# 51.net
KiCad netlist of a schematic drawn in Altium Designer
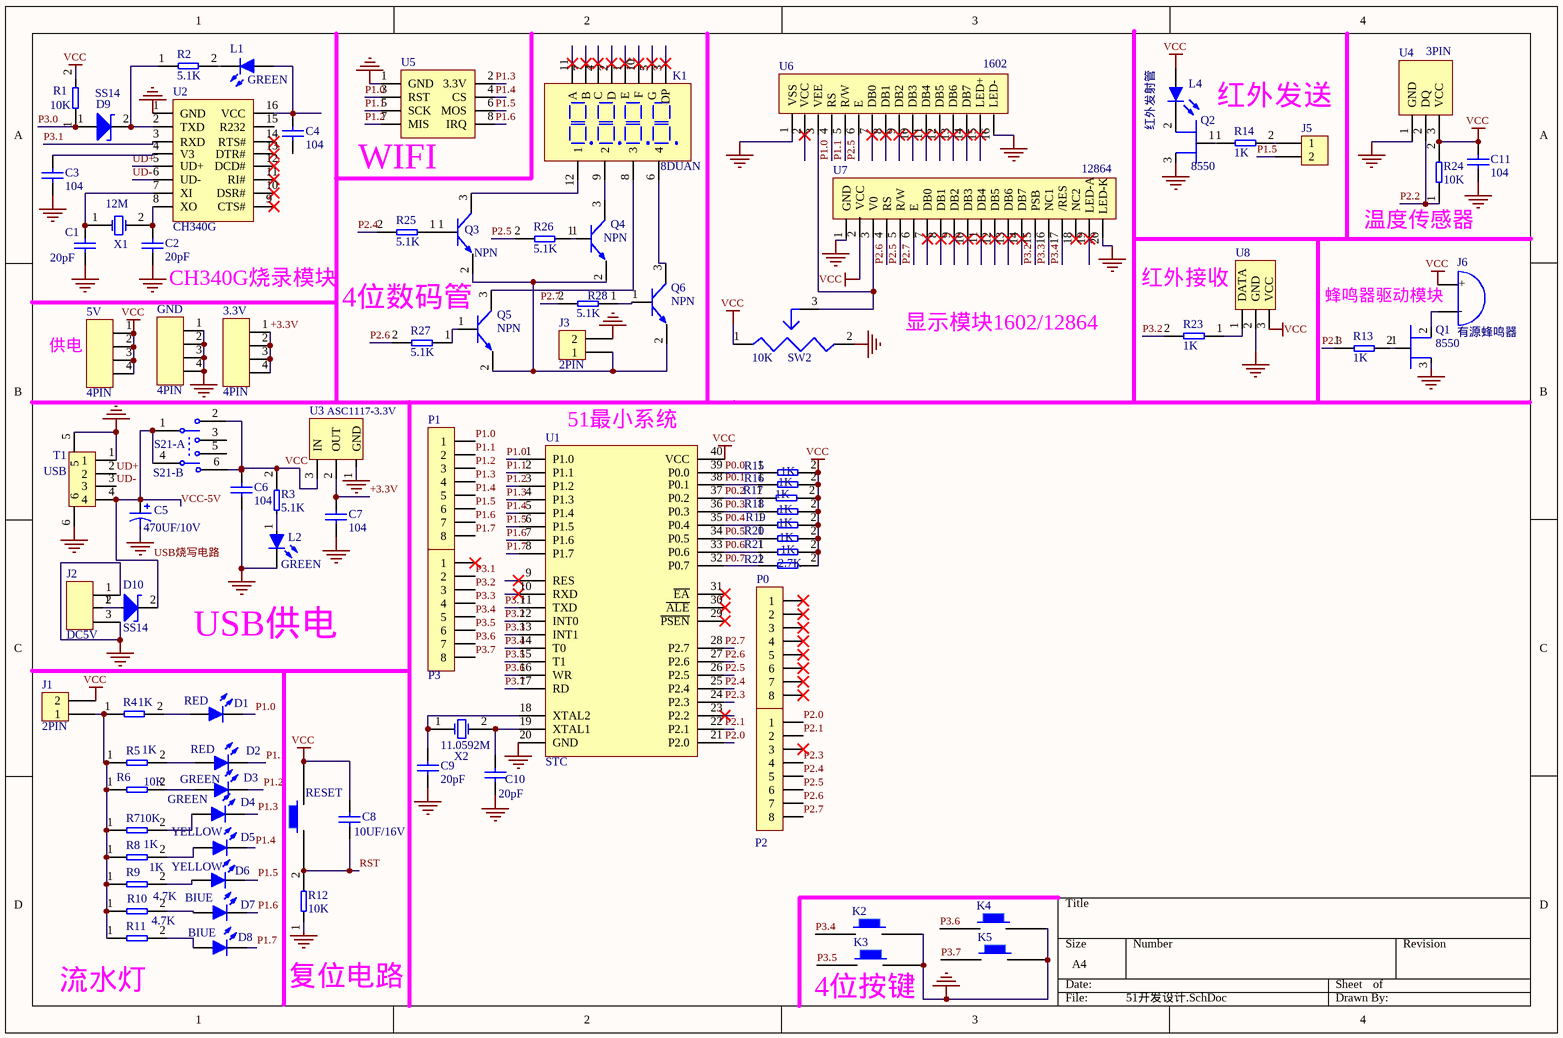
[diagram p0: 51开发设计.SchDoc]

(export (version "E")
  (design (tool "Eeschema 10.0.6"))
  (components
    (comp (ref "3.3V")
      (value "4PIN")
      (footprint "HDR2.54-LI-4P")
      (description "供电")
      (libsource (lib "完整集成") (part "Header-4Pin"))
    )
    (comp (ref "5V")
      (value "4PIN")
      (footprint "HDR2.54-LI-4P")
      (description "供电")
      (libsource (lib "完整集成") (part "Header-4Pin"))
    )
    (comp (ref "C1")
      (value "20pF")
      (footprint "C0603")
      (description "贴片电容")
      (libsource (lib "完整集成") (part "C0603"))
    )
    (comp (ref "C2")
      (value "20pF")
      (footprint "C0603")
      (description "贴片电容")
      (libsource (lib "完整集成") (part "C0603"))
    )
    (comp (ref "C3")
      (value "104")
      (footprint "C0603")
      (description "贴片电容")
      (libsource (lib "完整集成") (part "C0603"))
    )
    (comp (ref "C4")
      (value "104")
      (footprint "C0603")
      (description "贴片电容")
      (libsource (lib "完整集成") (part "C0603"))
    )
    (comp (ref "C5")
      (value "470UF/10V")
      (footprint "CAP-electr-1")
      (description "直插电解电容")
      (libsource (lib "完整集成") (part "CAP-EL-1"))
    )
    (comp (ref "C6")
      (value "104")
      (footprint "C0603")
      (description "贴片电容")
      (libsource (lib "完整集成") (part "C0603"))
    )
    (comp (ref "C7")
      (value "104")
      (footprint "C0603")
      (description "贴片电容")
      (libsource (lib "完整集成") (part "C0603"))
    )
    (comp (ref "C8")
      (value "10UF/16V")
      (footprint "CAP-electr")
      (description "直插电解电容")
      (libsource (lib "完整集成") (part "CAP-EL-2"))
    )
    (comp (ref "C9")
      (value "20pF")
      (footprint "C0603")
      (description "贴片电容")
      (libsource (lib "完整集成") (part "C0603"))
    )
    (comp (ref "C10")
      (value "20pF")
      (footprint "C0603")
      (description "贴片电容")
      (libsource (lib "完整集成") (part "C0603"))
    )
    (comp (ref "C11")
      (value "104")
      (footprint "C0603")
      (description "贴片电容")
      (libsource (lib "完整集成") (part "C0603"))
    )
    (comp (ref "D1")
      (value "RED")
      (footprint "LED-R")
      (description "贴片LED")
      (libsource (lib "完整集成") (part "LED-R"))
    )
    (comp (ref "D2")
      (value "RED")
      (footprint "LED-R")
      (description "贴片LED")
      (libsource (lib "完整集成") (part "LED-R"))
    )
    (comp (ref "D3")
      (value "GREEN")
      (footprint "LED-G")
      (description "贴片LED")
      (libsource (lib "完整集成") (part "LED-G"))
    )
    (comp (ref "D4")
      (value "GREEN")
      (footprint "LED-G")
      (description "贴片LED")
      (libsource (lib "完整集成") (part "LED-G"))
    )
    (comp (ref "D5")
      (value "YELLOW")
      (footprint "LED-Y")
      (description "贴片LED")
      (libsource (lib "完整集成") (part "LED-Y"))
    )
    (comp (ref "D6")
      (value "YELLOW")
      (footprint "LED-Y")
      (description "贴片LED")
      (libsource (lib "完整集成") (part "LED-Y"))
    )
    (comp (ref "D7")
      (value "BIUE")
      (footprint "LED-B")
      (description "贴片LED")
      (libsource (lib "完整集成") (part "LED-B"))
    )
    (comp (ref "D8")
      (value "BIUE")
      (footprint "LED-B")
      (description "贴片LED")
      (libsource (lib "完整集成") (part "LED-B"))
    )
    (comp (ref "D9")
      (value "SS14")
      (footprint "SOD-123")
      (description "二极管")
      (libsource (lib "完整集成") (part "Diode-2"))
    )
    (comp (ref "D10")
      (value "SS14")
      (footprint "SOD-123")
      (description "二极管")
      (libsource (lib "完整集成") (part "Diode-2"))
    )
    (comp (ref "GND")
      (value "4PIN")
      (footprint "HDR2.54-LI-4P")
      (description "供电")
      (libsource (lib "完整集成") (part "Header-4Pin"))
    )
    (comp (ref "J1")
      (value "2PIN")
      (footprint "HDR2.54-LI-2P")
      (description "跳线")
      (libsource (lib "") (part "Header-2Pin_1"))
    )
    (comp (ref "J2")
      (value "DC5V")
      (footprint "Power")
      (description "电源接口")
      (libsource (lib "完整集成") (part "Power"))
    )
    (comp (ref "J3")
      (value "2PIN")
      (footprint "HDR2.54-LI-2P")
      (description "跳线")
      (libsource (lib "") (part "Header-2Pin_1"))
    )
    (comp (ref "J5")
      (value "Header-2Pin")
      (footprint "HDR2.54-LI-2P")
      (description "跳线")
      (libsource (lib "完整集成") (part "Header-2Pin"))
    )
    (comp (ref "J6") (value "有源蜂鸣器") (footprint "Buzzer") (libsource (lib "完整集成") (part "Buzzer")))
    (comp (ref "K1")
      (value "8DUAN")
      (footprint "Digital tube")
      (description "数码管")
      (libsource (lib "完整集成") (part "DISP"))
    )
    (comp (ref "K2")
      (value "Key")
      (footprint "Key")
      (description "轻触按键")
      (libsource (lib "完整集成") (part "Key"))
    )
    (comp (ref "K3")
      (value "Key")
      (footprint "Key")
      (description "轻触按键")
      (libsource (lib "完整集成") (part "Key"))
    )
    (comp (ref "K4")
      (value "Key")
      (footprint "Key")
      (description "轻触按键")
      (libsource (lib "完整集成") (part "Key"))
    )
    (comp (ref "K5")
      (value "Key")
      (footprint "Key")
      (description "轻触按键")
      (libsource (lib "完整集成") (part "Key"))
    )
    (comp (ref "L1")
      (value "GREEN")
      (footprint "LED-G")
      (description "贴片LED")
      (libsource (lib "完整集成") (part "LED-G"))
    )
    (comp (ref "L2")
      (value "GREEN")
      (footprint "LED-G")
      (description "贴片LED")
      (libsource (lib "完整集成") (part "LED-G"))
    )
    (comp (ref "L4") (value "红外发射管") (footprint "LED infrar") (libsource (lib "完整集成") (part "LED infrar")))
    (comp (ref "P0")
      (value "Header-8Pin")
      (footprint "HDR2.54-LI-8P")
      (description "排针8")
      (libsource (lib "完整集成") (part "Header-8Pin"))
    )
    (comp (ref "P1")
      (value "Header-8Pin")
      (footprint "HDR2.54-LI-8P")
      (description "排针8")
      (libsource (lib "完整集成") (part "Header-8Pin"))
    )
    (comp (ref "P2")
      (value "Header-8Pin")
      (footprint "HDR2.54-LI-8P")
      (description "排针8")
      (libsource (lib "完整集成") (part "Header-8Pin"))
    )
    (comp (ref "P3")
      (value "Header-8Pin")
      (footprint "HDR2.54-LI-8P")
      (description "排针8")
      (libsource (lib "完整集成") (part "Header-8Pin"))
    )
    (comp (ref "Q1")
      (value "8550")
      (footprint "SOT-23-3")
      (description "三极管")
      (libsource (lib "完整集成") (part "Triode-3"))
    )
    (comp (ref "Q2")
      (value "8550")
      (footprint "SOT-23-3")
      (description "三极管")
      (libsource (lib "完整集成") (part "Triode-3"))
    )
    (comp (ref "Q3")
      (value "NPN")
      (footprint "SOT-23-3")
      (description "三极管")
      (libsource (lib "完整集成") (part "Triode-2"))
    )
    (comp (ref "Q4")
      (value "NPN")
      (footprint "SOT-23-3")
      (description "三极管")
      (libsource (lib "完整集成") (part "Triode-2"))
    )
    (comp (ref "Q5")
      (value "NPN")
      (footprint "SOT-23-3")
      (description "三极管")
      (libsource (lib "完整集成") (part "Triode-2"))
    )
    (comp (ref "Q6")
      (value "NPN")
      (footprint "SOT-23-3")
      (description "三极管")
      (libsource (lib "完整集成") (part "Triode-2"))
    )
    (comp (ref "R1")
      (value "10K")
      (footprint "R0603")
      (description "贴片电阻")
      (libsource (lib "完整集成") (part "R0603"))
    )
    (comp (ref "R2")
      (value "5.1K")
      (footprint "R0603")
      (description "贴片电阻")
      (libsource (lib "完整集成") (part "R0603"))
    )
    (comp (ref "R3")
      (value "5.1K")
      (footprint "R0603")
      (description "贴片电阻")
      (libsource (lib "完整集成") (part "R0603"))
    )
    (comp (ref "R4")
      (value "1K")
      (footprint "R0603")
      (description "贴片电阻")
      (libsource (lib "完整集成") (part "R0603"))
    )
    (comp (ref "R5")
      (value "1K")
      (footprint "R0603")
      (description "贴片电阻")
      (libsource (lib "完整集成") (part "R0603"))
    )
    (comp (ref "R6")
      (value "10K")
      (footprint "R0603")
      (description "贴片电阻")
      (libsource (lib "完整集成") (part "R0603"))
    )
    (comp (ref "R7")
      (value "10K")
      (footprint "R0603")
      (description "贴片电阻")
      (libsource (lib "完整集成") (part "R0603"))
    )
    (comp (ref "R8")
      (value "1K")
      (footprint "R0603")
      (description "贴片电阻")
      (libsource (lib "完整集成") (part "R0603"))
    )
    (comp (ref "R9")
      (value "1K")
      (footprint "R0603")
      (description "贴片电阻")
      (libsource (lib "完整集成") (part "R0603"))
    )
    (comp (ref "R10")
      (value "4.7K")
      (footprint "R0603")
      (description "贴片电阻")
      (libsource (lib "完整集成") (part "R0603"))
    )
    (comp (ref "R11")
      (value "4.7K")
      (footprint "R0603")
      (description "贴片电阻")
      (libsource (lib "完整集成") (part "R0603"))
    )
    (comp (ref "R12")
      (value "10K")
      (footprint "R0603")
      (description "贴片电阻")
      (libsource (lib "完整集成") (part "R0603"))
    )
    (comp (ref "R13")
      (value "1K")
      (footprint "R0603")
      (description "贴片电阻")
      (libsource (lib "完整集成") (part "R0603"))
    )
    (comp (ref "R14")
      (value "1K")
      (footprint "R0603")
      (description "贴片电阻")
      (libsource (lib "完整集成") (part "R0603"))
    )
    (comp (ref "R15")
      (value "1K")
      (footprint "R0603")
      (description "贴片电阻")
      (libsource (lib "完整集成") (part "R0603"))
    )
    (comp (ref "R16")
      (value "1K")
      (footprint "R0603")
      (description "贴片电阻")
      (libsource (lib "完整集成") (part "R0603"))
    )
    (comp (ref "R17")
      (value "1K")
      (footprint "R0603")
      (description "贴片电阻")
      (libsource (lib "完整集成") (part "R0603"))
    )
    (comp (ref "R18")
      (value "1K")
      (footprint "R0603")
      (description "贴片电阻")
      (libsource (lib "完整集成") (part "R0603"))
    )
    (comp (ref "R19")
      (value "1K")
      (footprint "R0603")
      (description "贴片电阻")
      (libsource (lib "完整集成") (part "R0603"))
    )
    (comp (ref "R20")
      (value "1K")
      (footprint "R0603")
      (description "贴片电阻")
      (libsource (lib "完整集成") (part "R0603"))
    )
    (comp (ref "R21")
      (value "1K")
      (footprint "R0603")
      (description "贴片电阻")
      (libsource (lib "完整集成") (part "R0603"))
    )
    (comp (ref "R22")
      (value "2.7K")
      (footprint "R0603")
      (description "贴片电阻")
      (libsource (lib "完整集成") (part "R0603"))
    )
    (comp (ref "R23")
      (value "1K")
      (footprint "R0603")
      (description "贴片电阻")
      (libsource (lib "完整集成") (part "R0603"))
    )
    (comp (ref "R24")
      (value "10K")
      (footprint "R0603")
      (description "贴片电阻")
      (libsource (lib "完整集成") (part "R0603"))
    )
    (comp (ref "R25")
      (value "5.1K")
      (footprint "R0603")
      (description "贴片电阻")
      (libsource (lib "完整集成") (part "R0603"))
    )
    (comp (ref "R26")
      (value "5.1K")
      (footprint "R0603")
      (description "贴片电阻")
      (libsource (lib "完整集成") (part "R0603"))
    )
    (comp (ref "R27")
      (value "5.1K")
      (footprint "R0603")
      (description "贴片电阻")
      (libsource (lib "完整集成") (part "R0603"))
    )
    (comp (ref "R28")
      (value "5.1K")
      (footprint "R0603")
      (description "贴片电阻")
      (libsource (lib "完整集成") (part "R0603"))
    )
    (comp (ref "RESET")
      (value "Key")
      (footprint "Key")
      (description "轻触按键")
      (libsource (lib "") (part "Key_1"))
    )
    (comp (ref "S21-A")
      (value "S21-B")
      (footprint "SW")
      (description "开关按键")
      (libsource (lib "完整集成") (part "SW"))
    )
    (comp (ref "SW2")
      (value "10K")
      (footprint "Rheostat")
      (description "可调电位器")
      (libsource (lib "完整集成") (part "Rheostat"))
    )
    (comp (ref "T1")
      (value "USB")
      (footprint "USB-MICRO_D")
      (description "USB写入")
      (libsource (lib "完整集成") (part "Micro-usb"))
    )
    (comp (ref "U1")
      (value "STC")
      (footprint "STC89C5X")
      (description "单片机整个")
      (libsource (lib "完整集成") (part "STC89C5X"))
    )
    (comp (ref "U2")
      (value "CH340G")
      (footprint "CH340G")
      (description "电源芯片")
      (libsource (lib "完整集成") (part "CH340G"))
    )
    (comp (ref "U3")
      (value "ASC1117-3.3V")
      (footprint "SOT-223")
      (description "三极管-烧写")
      (libsource (lib "完整集成") (part "Triode-1"))
    )
    (comp (ref "U4")
      (value "3PIN")
      (footprint "HDR2.54-Y-LI-3P")
      (description "温度传感器")
      (libsource (lib "完整集成") (part "Header-3Pin"))
    )
    (comp (ref "U5")
      (value "WIFI")
      (footprint "WiFi Mod")
      (description "WiFi模块")
      (libsource (lib "完整集成") (part "WIFI Module"))
    )
    (comp (ref "U6")
      (value "1602")
      (footprint "HDR2.54-M-LI-16P")
      (description "排母16")
      (libsource (lib "完整集成") (part "Header-16P"))
    )
    (comp (ref "U7")
      (value "12864")
      (footprint "HDR2.54-M-LI-20P")
      (description "排母20")
      (libsource (lib "完整集成") (part "Header-20P"))
    )
    (comp (ref "U8")
      (value "Header-3Pin-1")
      (footprint "HDR2.54-Y-LI-3P")
      (description "红外接收")
      (libsource (lib "完整集成") (part "Header-3Pin-1"))
    )
    (comp (ref "X1")
      (value "12M")
      (footprint "XTAL")
      (description "直插晶振")
      (libsource (lib "完整集成") (part "XTAL"))
    )
    (comp (ref "X2")
      (value "11.0592M")
      (footprint "XTAL")
      (description "直插晶振")
      (libsource (lib "完整集成") (part "XTAL"))
    )
  )
  (nets
    (net (code "1") (name "/+3.3V") (class "Default")
      (node (ref "3.3V") (pin "1") (pinfunction "1_1") (pintype "passive"))
      (node (ref "3.3V") (pin "2") (pinfunction "2_2") (pintype "passive"))
      (node (ref "3.3V") (pin "3") (pinfunction "3_3") (pintype "passive"))
      (node (ref "3.3V") (pin "4") (pinfunction "4_4") (pintype "passive"))
      (node (ref "C7") (pin "2") (pinfunction "2_2") (pintype "passive"))
      (node (ref "U3") (pin "2") (pinfunction "OUT_2") (pintype "passive"))
    )
    (net (code "2") (name "/P0.0") (class "Default")
      (node (ref "R15") (pin "1") (pinfunction "1_1") (pintype "passive"))
      (node (ref "U1") (pin "39") (pinfunction "P0.0_39") (pintype "passive"))
    )
    (net (code "3") (name "/P0.1") (class "Default")
      (node (ref "R16") (pin "1") (pinfunction "1_1") (pintype "passive"))
      (node (ref "U1") (pin "38") (pinfunction "P0.1_38") (pintype "passive"))
    )
    (net (code "4") (name "/P0.2") (class "Default")
      (node (ref "R17") (pin "1") (pinfunction "1_1") (pintype "passive"))
      (node (ref "U1") (pin "37") (pinfunction "P0.2_37") (pintype "passive"))
    )
    (net (code "5") (name "/P0.3") (class "Default")
      (node (ref "R18") (pin "1") (pinfunction "1_1") (pintype "passive"))
      (node (ref "U1") (pin "36") (pinfunction "P0.3_36") (pintype "passive"))
    )
    (net (code "6") (name "/P0.4") (class "Default")
      (node (ref "R19") (pin "1") (pinfunction "1_1") (pintype "passive"))
      (node (ref "U1") (pin "35") (pinfunction "P0.4_35") (pintype "passive"))
    )
    (net (code "7") (name "/P0.5") (class "Default")
      (node (ref "R20") (pin "1") (pinfunction "1_1") (pintype "passive"))
      (node (ref "U1") (pin "34") (pinfunction "P0.5_34") (pintype "passive"))
    )
    (net (code "8") (name "/P0.6") (class "Default")
      (node (ref "R21") (pin "1") (pinfunction "1_1") (pintype "passive"))
      (node (ref "U1") (pin "33") (pinfunction "P0.6_33") (pintype "passive"))
    )
    (net (code "9") (name "/P0.7") (class "Default")
      (node (ref "R22") (pin "1") (pinfunction "1_1") (pintype "passive"))
      (node (ref "U1") (pin "32") (pinfunction "P0.7_32") (pintype "passive"))
    )
    (net (code "10") (name "/P1.0") (class "Default")
      (node (ref "D1") (pin "2") (pinfunction "K_2") (pintype "passive"))
      (node (ref "P1") (pin "1") (pinfunction "1_1") (pintype "passive"))
      (node (ref "U1") (pin "1") (pinfunction "P1.0_1") (pintype "passive"))
      (node (ref "U5") (pin "3") (pinfunction "RST_3") (pintype "passive"))
      (node (ref "U6") (pin "4") (pinfunction "RS_4") (pintype "passive"))
    )
    (net (code "11") (name "/P1.1") (class "Default")
      (node (ref "D2") (pin "2") (pinfunction "K_2") (pintype "passive"))
      (node (ref "P1") (pin "2") (pinfunction "2_2") (pintype "passive"))
      (node (ref "U1") (pin "2") (pinfunction "P1.1_2") (pintype "passive"))
      (node (ref "U5") (pin "5") (pinfunction "SCK_5") (pintype "passive"))
      (node (ref "U6") (pin "5") (pinfunction "R/W_5") (pintype "passive"))
    )
    (net (code "12") (name "/P1.2") (class "Default")
      (node (ref "D3") (pin "2") (pinfunction "K_2") (pintype "passive"))
      (node (ref "P1") (pin "3") (pinfunction "3_3") (pintype "passive"))
      (node (ref "U1") (pin "3") (pinfunction "P1.2_3") (pintype "passive"))
      (node (ref "U5") (pin "7") (pinfunction "MIS_7") (pintype "passive"))
    )
    (net (code "13") (name "/P1.3") (class "Default")
      (node (ref "D4") (pin "2") (pinfunction "K_2") (pintype "passive"))
      (node (ref "P1") (pin "4") (pinfunction "4_4") (pintype "passive"))
      (node (ref "U1") (pin "4") (pinfunction "P1.3_4") (pintype "passive"))
      (node (ref "U5") (pin "2") (pinfunction "3.3V_2") (pintype "passive"))
    )
    (net (code "14") (name "/P1.4") (class "Default")
      (node (ref "D5") (pin "2") (pinfunction "K_2") (pintype "passive"))
      (node (ref "P1") (pin "5") (pinfunction "5_5") (pintype "passive"))
      (node (ref "U1") (pin "5") (pinfunction "P1.4_5") (pintype "passive"))
      (node (ref "U5") (pin "4") (pinfunction "CS_4") (pintype "passive"))
    )
    (net (code "15") (name "/P1.5") (class "Default")
      (node (ref "D6") (pin "2") (pinfunction "K_2") (pintype "passive"))
      (node (ref "J5") (pin "2") (pinfunction "2_2") (pintype "passive"))
      (node (ref "P1") (pin "6") (pinfunction "6_6") (pintype "passive"))
      (node (ref "U1") (pin "6") (pinfunction "P1.5_6") (pintype "passive"))
      (node (ref "U5") (pin "6") (pinfunction "MOS_6") (pintype "passive"))
    )
    (net (code "16") (name "/P1.6") (class "Default")
      (node (ref "D7") (pin "2") (pinfunction "K_2") (pintype "passive"))
      (node (ref "P1") (pin "7") (pinfunction "7_7") (pintype "passive"))
      (node (ref "U1") (pin "7") (pinfunction "P1.6_7") (pintype "passive"))
      (node (ref "U5") (pin "8") (pinfunction "IRQ_8") (pintype "passive"))
    )
    (net (code "17") (name "/P1.7") (class "Default")
      (node (ref "D8") (pin "2") (pinfunction "K_2") (pintype "passive"))
      (node (ref "P1") (pin "8") (pinfunction "8_8") (pintype "passive"))
      (node (ref "U1") (pin "8") (pinfunction "P1.7_8") (pintype "passive"))
    )
    (net (code "18") (name "/P2.0") (class "Default")
      (node (ref "P2") (pin "1") (pinfunction "1_1") (pintype "passive"))
      (node (ref "U1") (pin "21") (pinfunction "P2.0_21") (pintype "passive"))
    )
    (net (code "19") (name "/P2.1") (class "Default")
      (node (ref "P2") (pin "2") (pinfunction "2_2") (pintype "passive"))
      (node (ref "U1") (pin "22") (pinfunction "P2.1_22") (pintype "passive"))
    )
    (net (code "20") (name "/P2.2") (class "Default")
      (node (ref "R24") (pin "1") (pinfunction "1_1") (pintype "passive"))
      (node (ref "U4") (pin "2") (pinfunction "DQ_2") (pintype "passive"))
    )
    (net (code "21") (name "/P2.3") (class "Default")
      (node (ref "P2") (pin "4") (pinfunction "4_4") (pintype "passive"))
      (node (ref "R13") (pin "1") (pinfunction "1_1") (pintype "passive"))
      (node (ref "U1") (pin "24") (pinfunction "P2.3_24") (pintype "passive"))
    )
    (net (code "22") (name "/P2.4") (class "Default")
      (node (ref "P2") (pin "5") (pinfunction "5_5") (pintype "passive"))
      (node (ref "R25") (pin "2") (pinfunction "2_2") (pintype "passive"))
      (node (ref "U1") (pin "25") (pinfunction "P2.4_25") (pintype "passive"))
    )
    (net (code "23") (name "/P2.5") (class "Default")
      (node (ref "P2") (pin "6") (pinfunction "6_6") (pintype "passive"))
      (node (ref "R26") (pin "2") (pinfunction "2_2") (pintype "passive"))
      (node (ref "U1") (pin "26") (pinfunction "P2.5_26") (pintype "passive"))
      (node (ref "U6") (pin "6") (pinfunction "E_6") (pintype "passive"))
      (node (ref "U7") (pin "5") (pinfunction "R/W_5") (pintype "passive"))
    )
    (net (code "24") (name "/P2.6") (class "Default")
      (node (ref "P2") (pin "7") (pinfunction "7_7") (pintype "passive"))
      (node (ref "R27") (pin "2") (pinfunction "2_2") (pintype "passive"))
      (node (ref "U1") (pin "27") (pinfunction "P2.6_27") (pintype "passive"))
      (node (ref "U7") (pin "4") (pinfunction "RS_4") (pintype "passive"))
    )
    (net (code "25") (name "/P2.7") (class "Default")
      (node (ref "P2") (pin "8") (pinfunction "8_8") (pintype "passive"))
      (node (ref "R28") (pin "2") (pinfunction "2_2") (pintype "passive"))
      (node (ref "U1") (pin "28") (pinfunction "P2.7_28") (pintype "passive"))
      (node (ref "U7") (pin "6") (pinfunction "E_6") (pintype "passive"))
    )
    (net (code "26") (name "/P3.0") (class "Default")
      (node (ref "D9") (pin "1") (pinfunction "1_1") (pintype "passive"))
      (node (ref "R1") (pin "1") (pinfunction "1_1") (pintype "passive"))
    )
    (net (code "27") (name "/P3.1") (class "Default")
      (node (ref "P3") (pin "2") (pinfunction "2_2") (pintype "passive"))
      (node (ref "U1") (pin "11") (pinfunction "TXD_11") (pintype "passive"))
      (node (ref "U2") (pin "3") (pinfunction "RXD_3") (pintype "passive"))
    )
    (net (code "28") (name "/P3.2") (class "Default")
      (node (ref "P3") (pin "3") (pinfunction "3_3") (pintype "passive"))
      (node (ref "R23") (pin "2") (pinfunction "2_2") (pintype "passive"))
      (node (ref "U1") (pin "12") (pinfunction "INT0_12") (pintype "passive"))
      (node (ref "U7") (pin "15") (pinfunction "PSB_15") (pintype "passive"))
    )
    (net (code "29") (name "/P3.3") (class "Default")
      (node (ref "P3") (pin "4") (pinfunction "4_4") (pintype "passive"))
      (node (ref "U1") (pin "13") (pinfunction "INT1_13") (pintype "passive"))
      (node (ref "U7") (pin "16") (pinfunction "NC1_16") (pintype "passive"))
    )
    (net (code "30") (name "/P3.4") (class "Default")
      (node (ref "K2") (pin "1") (pinfunction "1_1") (pintype "passive"))
      (node (ref "P3") (pin "5") (pinfunction "5_5") (pintype "passive"))
      (node (ref "U1") (pin "14") (pinfunction "T0_14") (pintype "passive"))
      (node (ref "U7") (pin "17") (pinfunction "/RES_17") (pintype "passive"))
    )
    (net (code "31") (name "/P3.5") (class "Default")
      (node (ref "K3") (pin "1") (pinfunction "1_1") (pintype "passive"))
      (node (ref "P3") (pin "6") (pinfunction "6_6") (pintype "passive"))
      (node (ref "U1") (pin "15") (pinfunction "T1_15") (pintype "passive"))
    )
    (net (code "32") (name "/P3.6") (class "Default")
      (node (ref "K4") (pin "1") (pinfunction "1_1") (pintype "passive"))
      (node (ref "P3") (pin "7") (pinfunction "7_7") (pintype "passive"))
      (node (ref "U1") (pin "16") (pinfunction "WR_16") (pintype "passive"))
    )
    (net (code "33") (name "/P3.7") (class "Default")
      (node (ref "K5") (pin "1") (pinfunction "1_1") (pintype "passive"))
      (node (ref "P3") (pin "8") (pinfunction "8_8") (pintype "passive"))
      (node (ref "U1") (pin "17") (pinfunction "RD_17") (pintype "passive"))
    )
    (net (code "34") (name "/RST") (class "Default")
      (node (ref "C8") (pin "1") (pinfunction "1_1") (pintype "passive"))
      (node (ref "R12") (pin "2") (pinfunction "2_2") (pintype "passive"))
      (node (ref "RESET") (pin "1") (pinfunction "1_1") (pintype "passive"))
    )
    (net (code "35") (name "/UD+") (class "Default")
      (node (ref "T1") (pin "2") (pinfunction "2_2") (pintype "passive"))
      (node (ref "U2") (pin "5") (pinfunction "UD+_5") (pintype "passive"))
    )
    (net (code "36") (name "/UD-") (class "Default")
      (node (ref "T1") (pin "3") (pinfunction "3_3") (pintype "passive"))
      (node (ref "U2") (pin "6") (pinfunction "UD-_6") (pintype "passive"))
    )
    (net (code "37") (name "/USB烧写电路") (class "Default")
      (node (ref "C5") (pin "1") (pinfunction "1_1") (pintype "passive"))
      (node (ref "D10") (pin "2") (pinfunction "2_2") (pintype "passive"))
      (node (ref "S21-A") (pin "1") (pinfunction "1_1") (pintype "passive"))
      (node (ref "S21-A") (pin "4") (pinfunction "4_4") (pintype "passive"))
      (node (ref "T1") (pin "4") (pinfunction "4_4") (pintype "passive"))
    )
    (net (code "38") (name "GND") (class "Default")
      (node (ref "C1") (pin "1") (pinfunction "1_1") (pintype "passive"))
      (node (ref "C10") (pin "1") (pinfunction "1_1") (pintype "passive"))
      (node (ref "C11") (pin "1") (pinfunction "1_1") (pintype "passive"))
      (node (ref "C2") (pin "1") (pinfunction "1_1") (pintype "passive"))
      (node (ref "C3") (pin "1") (pinfunction "1_1") (pintype "passive"))
      (node (ref "C5") (pin "2") (pinfunction "2_2") (pintype "passive"))
      (node (ref "C6") (pin "1") (pinfunction "1_1") (pintype "passive"))
      (node (ref "C7") (pin "1") (pinfunction "1_1") (pintype "passive"))
      (node (ref "C9") (pin "1") (pinfunction "1_1") (pintype "passive"))
      (node (ref "GND") (pin "1") (pinfunction "1_1") (pintype "passive"))
      (node (ref "GND") (pin "2") (pinfunction "2_2") (pintype "passive"))
      (node (ref "GND") (pin "3") (pinfunction "3_3") (pintype "passive"))
      (node (ref "GND") (pin "4") (pinfunction "4_4") (pintype "passive"))
      (node (ref "J2") (pin "1") (pinfunction "1_1") (pintype "passive"))
      (node (ref "J2") (pin "3") (pinfunction "3_3") (pintype "passive"))
      (node (ref "J3") (pin "2") (pinfunction "2_2") (pintype "passive"))
      (node (ref "K2") (pin "2") (pinfunction "2_2") (pintype "passive"))
      (node (ref "K3") (pin "2") (pinfunction "2_2") (pintype "passive"))
      (node (ref "K4") (pin "2") (pinfunction "2_2") (pintype "passive"))
      (node (ref "K5") (pin "2") (pinfunction "2_2") (pintype "passive"))
      (node (ref "L2") (pin "2") (pinfunction "K_2") (pintype "passive"))
      (node (ref "Q1") (pin "3") (pinfunction "3_3") (pintype "passive"))
      (node (ref "Q2") (pin "3") (pinfunction "3_3") (pintype "passive"))
      (node (ref "R12") (pin "1") (pinfunction "1_1") (pintype "passive"))
      (node (ref "SW2") (pin "2") (pinfunction "2_2") (pintype "passive"))
      (node (ref "T1") (pin "1") (pinfunction "1_1") (pintype "passive"))
      (node (ref "T1") (pin "5") (pinfunction "5_5") (pintype "passive"))
      (node (ref "T1") (pin "6") (pinfunction "6_6") (pintype "passive"))
      (node (ref "U1") (pin "20") (pinfunction "GND_20") (pintype "passive"))
      (node (ref "U2") (pin "1") (pinfunction "GND_1") (pintype "passive"))
      (node (ref "U3") (pin "1") (pinfunction "GND_1") (pintype "passive"))
      (node (ref "U4") (pin "1") (pinfunction "GND_1") (pintype "passive"))
      (node (ref "U5") (pin "1") (pinfunction "GND_1") (pintype "passive"))
      (node (ref "U6") (pin "1") (pinfunction "VSS_1") (pintype "passive"))
      (node (ref "U6") (pin "16") (pinfunction "LED-_16") (pintype "passive"))
      (node (ref "U7") (pin "1") (pinfunction "GND_1") (pintype "passive"))
      (node (ref "U7") (pin "20") (pinfunction "LED-K_20") (pintype "passive"))
      (node (ref "U8") (pin "2") (pinfunction "GND_2") (pintype "passive"))
    )
    (net (code "39") (name "Net-(D1-A)") (class "Default")
      (node (ref "D1") (pin "1") (pinfunction "A_1") (pintype "passive"))
      (node (ref "R4") (pin "2") (pinfunction "2_2") (pintype "passive"))
    )
    (net (code "40") (name "Net-(D2-A)") (class "Default")
      (node (ref "D2") (pin "1") (pinfunction "A_1") (pintype "passive"))
      (node (ref "R5") (pin "2") (pinfunction "2_2") (pintype "passive"))
    )
    (net (code "41") (name "Net-(D3-A)") (class "Default")
      (node (ref "D3") (pin "1") (pinfunction "A_1") (pintype "passive"))
      (node (ref "R6") (pin "2") (pinfunction "2_2") (pintype "passive"))
    )
    (net (code "42") (name "Net-(D4-A)") (class "Default")
      (node (ref "D4") (pin "1") (pinfunction "A_1") (pintype "passive"))
      (node (ref "R7") (pin "2") (pinfunction "2_2") (pintype "passive"))
    )
    (net (code "43") (name "Net-(D5-A)") (class "Default")
      (node (ref "D5") (pin "1") (pinfunction "A_1") (pintype "passive"))
      (node (ref "R8") (pin "2") (pinfunction "2_2") (pintype "passive"))
    )
    (net (code "44") (name "Net-(D6-A)") (class "Default")
      (node (ref "D6") (pin "1") (pinfunction "A_1") (pintype "passive"))
      (node (ref "R9") (pin "2") (pinfunction "2_2") (pintype "passive"))
    )
    (net (code "45") (name "Net-(D7-A)") (class "Default")
      (node (ref "D7") (pin "1") (pinfunction "A_1") (pintype "passive"))
      (node (ref "R10") (pin "2") (pinfunction "2_2") (pintype "passive"))
    )
    (net (code "46") (name "Net-(D8-A)") (class "Default")
      (node (ref "D8") (pin "1") (pinfunction "A_1") (pintype "passive"))
      (node (ref "R11") (pin "2") (pinfunction "2_2") (pintype "passive"))
    )
    (net (code "47") (name "Net-(D10-Pad1)") (class "Default")
      (node (ref "D10") (pin "1") (pinfunction "1_1") (pintype "passive"))
      (node (ref "J2") (pin "2") (pinfunction "2_2") (pintype "passive"))
    )
    (net (code "48") (name "Net-(J1-Pad1)") (class "Default")
      (node (ref "J1") (pin "1") (pinfunction "1_1") (pintype "passive"))
      (node (ref "R10") (pin "1") (pinfunction "1_1") (pintype "passive"))
      (node (ref "R11") (pin "1") (pinfunction "1_1") (pintype "passive"))
      (node (ref "R4") (pin "1") (pinfunction "1_1") (pintype "passive"))
      (node (ref "R5") (pin "1") (pinfunction "1_1") (pintype "passive"))
      (node (ref "R6") (pin "1") (pinfunction "1_1") (pintype "passive"))
      (node (ref "R7") (pin "1") (pinfunction "1_1") (pintype "passive"))
      (node (ref "R8") (pin "1") (pinfunction "1_1") (pintype "passive"))
      (node (ref "R9") (pin "1") (pinfunction "1_1") (pintype "passive"))
    )
    (net (code "49") (name "Net-(J3-Pad1)") (class "Default")
      (node (ref "J3") (pin "1") (pinfunction "1_1") (pintype "passive"))
      (node (ref "Q3") (pin "2") (pinfunction "2_2") (pintype "passive"))
      (node (ref "Q4") (pin "2") (pinfunction "2_2") (pintype "passive"))
      (node (ref "Q5") (pin "2") (pinfunction "2_2") (pintype "passive"))
      (node (ref "Q6") (pin "2") (pinfunction "2_2") (pintype "passive"))
    )
    (net (code "50") (name "Net-(J5-Pad1)") (class "Default")
      (node (ref "J5") (pin "1") (pinfunction "1_1") (pintype "passive"))
      (node (ref "R14") (pin "2") (pinfunction "2_2") (pintype "passive"))
    )
    (net (code "51") (name "Net-(J6-B)") (class "Default")
      (node (ref "J6") (pin "2") (pinfunction "B_2") (pintype "passive"))
      (node (ref "Q1") (pin "2") (pinfunction "2_2") (pintype "passive"))
    )
    (net (code "52") (name "Net-(K1-1)") (class "Default")
      (node (ref "K1") (pin "12") (pinfunction "1_12") (pintype "passive"))
      (node (ref "Q3") (pin "3") (pinfunction "3_3") (pintype "passive"))
    )
    (net (code "53") (name "Net-(K1-2)") (class "Default")
      (node (ref "K1") (pin "9") (pinfunction "2_9") (pintype "passive"))
      (node (ref "Q4") (pin "3") (pinfunction "3_3") (pintype "passive"))
    )
    (net (code "54") (name "Net-(K1-3)") (class "Default")
      (node (ref "K1") (pin "8") (pinfunction "3_8") (pintype "passive"))
      (node (ref "Q5") (pin "3") (pinfunction "3_3") (pintype "passive"))
    )
    (net (code "55") (name "Net-(K1-4)") (class "Default")
      (node (ref "K1") (pin "6") (pinfunction "4_6") (pintype "passive"))
      (node (ref "Q6") (pin "3") (pinfunction "3_3") (pintype "passive"))
    )
    (net (code "56") (name "Net-(L1-A)") (class "Default")
      (node (ref "C4") (pin "2") (pinfunction "2_2") (pintype "passive"))
      (node (ref "L1") (pin "1") (pinfunction "A_1") (pintype "passive"))
      (node (ref "U2") (pin "16") (pinfunction "VCC_16") (pintype "passive"))
    )
    (net (code "57") (name "Net-(L1-K)") (class "Default")
      (node (ref "L1") (pin "2") (pinfunction "K_2") (pintype "passive"))
      (node (ref "R2") (pin "2") (pinfunction "2_2") (pintype "passive"))
    )
    (net (code "58") (name "Net-(L2-A)") (class "Default")
      (node (ref "L2") (pin "1") (pinfunction "A_1") (pintype "passive"))
      (node (ref "R3") (pin "1") (pinfunction "1_1") (pintype "passive"))
    )
    (net (code "59") (name "Net-(L4-K)") (class "Default")
      (node (ref "L4") (pin "2") (pinfunction "K_2") (pintype "passive"))
      (node (ref "Q2") (pin "2") (pinfunction "2_2") (pintype "passive"))
    )
    (net (code "60") (name "Net-(Q1-Pad1)") (class "Default")
      (node (ref "Q1") (pin "1") (pinfunction "1_1") (pintype "passive"))
      (node (ref "R13") (pin "2") (pinfunction "2_2") (pintype "passive"))
    )
    (net (code "61") (name "Net-(Q2-Pad1)") (class "Default")
      (node (ref "Q2") (pin "1") (pinfunction "1_1") (pintype "passive"))
      (node (ref "R14") (pin "1") (pinfunction "1_1") (pintype "passive"))
    )
    (net (code "62") (name "Net-(Q3-Pad1)") (class "Default")
      (node (ref "Q3") (pin "1") (pinfunction "1_1") (pintype "passive"))
      (node (ref "R25") (pin "1") (pinfunction "1_1") (pintype "passive"))
    )
    (net (code "63") (name "Net-(Q4-Pad1)") (class "Default")
      (node (ref "Q4") (pin "1") (pinfunction "1_1") (pintype "passive"))
      (node (ref "R26") (pin "1") (pinfunction "1_1") (pintype "passive"))
    )
    (net (code "64") (name "Net-(Q5-Pad1)") (class "Default")
      (node (ref "Q5") (pin "1") (pinfunction "1_1") (pintype "passive"))
      (node (ref "R27") (pin "1") (pinfunction "1_1") (pintype "passive"))
    )
    (net (code "65") (name "Net-(Q6-Pad1)") (class "Default")
      (node (ref "Q6") (pin "1") (pinfunction "1_1") (pintype "passive"))
      (node (ref "R28") (pin "1") (pinfunction "1_1") (pintype "passive"))
    )
    (net (code "66") (name "Net-(U1-XTAL1)") (class "Default")
      (node (ref "C10") (pin "2") (pinfunction "2_2") (pintype "passive"))
      (node (ref "U1") (pin "19") (pinfunction "XTAL1_19") (pintype "passive"))
      (node (ref "X2") (pin "2") (pinfunction "OSC2_2") (pintype "passive"))
    )
    (net (code "67") (name "Net-(U1-XTAL2)") (class "Default")
      (node (ref "C9") (pin "2") (pinfunction "2_2") (pintype "passive"))
      (node (ref "U1") (pin "18") (pinfunction "XTAL2_18") (pintype "passive"))
      (node (ref "X2") (pin "1") (pinfunction "OSC1_1") (pintype "passive"))
    )
    (net (code "68") (name "Net-(U2-TXD)") (class "Default")
      (node (ref "D9") (pin "2") (pinfunction "2_2") (pintype "passive"))
      (node (ref "R2") (pin "1") (pinfunction "1_1") (pintype "passive"))
      (node (ref "U2") (pin "2") (pinfunction "TXD_2") (pintype "passive"))
    )
    (net (code "69") (name "Net-(U2-V3)") (class "Default")
      (node (ref "C3") (pin "2") (pinfunction "2_2") (pintype "passive"))
      (node (ref "U2") (pin "4") (pinfunction "V3_4") (pintype "passive"))
    )
    (net (code "70") (name "Net-(U2-XI)") (class "Default")
      (node (ref "C1") (pin "2") (pinfunction "2_2") (pintype "passive"))
      (node (ref "U2") (pin "7") (pinfunction "XI_7") (pintype "passive"))
      (node (ref "X1") (pin "1") (pinfunction "OSC1_1") (pintype "passive"))
    )
    (net (code "71") (name "Net-(U2-XO)") (class "Default")
      (node (ref "C2") (pin "2") (pinfunction "2_2") (pintype "passive"))
      (node (ref "U2") (pin "8") (pinfunction "XO_8") (pintype "passive"))
      (node (ref "X1") (pin "2") (pinfunction "OSC2_2") (pintype "passive"))
    )
    (net (code "72") (name "Net-(U6-VEE)") (class "Default")
      (node (ref "SW2") (pin "3") (pinfunction "3_3") (pintype "passive"))
      (node (ref "U6") (pin "3") (pinfunction "VEE_3") (pintype "passive"))
      (node (ref "U7") (pin "3") (pinfunction "V0_3") (pintype "passive"))
    )
    (net (code "73") (name "Net-(U8-DATA)") (class "Default")
      (node (ref "R23") (pin "1") (pinfunction "1_1") (pintype "passive"))
      (node (ref "U8") (pin "1") (pinfunction "DATA_1") (pintype "passive"))
    )
    (net (code "74") (name "VCC") (class "Default")
      (node (ref "5V") (pin "1") (pinfunction "1_1") (pintype "passive"))
      (node (ref "5V") (pin "2") (pinfunction "2_2") (pintype "passive"))
      (node (ref "5V") (pin "3") (pinfunction "3_3") (pintype "passive"))
      (node (ref "5V") (pin "4") (pinfunction "4_4") (pintype "passive"))
      (node (ref "C11") (pin "2") (pinfunction "2_2") (pintype "passive"))
      (node (ref "C6") (pin "2") (pinfunction "2_2") (pintype "passive"))
      (node (ref "C8") (pin "2") (pinfunction "2_2") (pintype "passive"))
      (node (ref "J1") (pin "2") (pinfunction "2_2") (pintype "passive"))
      (node (ref "J6") (pin "1") (pinfunction "A_1") (pintype "passive"))
      (node (ref "L4") (pin "1") (pinfunction "A_1") (pintype "passive"))
      (node (ref "R1") (pin "2") (pinfunction "2_2") (pintype "passive"))
      (node (ref "R15") (pin "2") (pinfunction "2_2") (pintype "passive"))
      (node (ref "R16") (pin "2") (pinfunction "2_2") (pintype "passive"))
      (node (ref "R17") (pin "2") (pinfunction "2_2") (pintype "passive"))
      (node (ref "R18") (pin "2") (pinfunction "2_2") (pintype "passive"))
      (node (ref "R19") (pin "2") (pinfunction "2_2") (pintype "passive"))
      (node (ref "R20") (pin "2") (pinfunction "2_2") (pintype "passive"))
      (node (ref "R21") (pin "2") (pinfunction "2_2") (pintype "passive"))
      (node (ref "R22") (pin "2") (pinfunction "2_2") (pintype "passive"))
      (node (ref "R24") (pin "2") (pinfunction "2_2") (pintype "passive"))
      (node (ref "R3") (pin "2") (pinfunction "2_2") (pintype "passive"))
      (node (ref "RESET") (pin "2") (pinfunction "2_2") (pintype "passive"))
      (node (ref "S21-A") (pin "2") (pinfunction "2_2") (pintype "passive"))
      (node (ref "S21-A") (pin "6") (pinfunction "6_6") (pintype "passive"))
      (node (ref "SW2") (pin "1") (pinfunction "1_1") (pintype "passive"))
      (node (ref "U1") (pin "40") (pinfunction "VCC_40") (pintype "passive"))
      (node (ref "U3") (pin "3") (pinfunction "IN_3") (pintype "passive"))
      (node (ref "U4") (pin "3") (pinfunction "VCC_3") (pintype "passive"))
      (node (ref "U7") (pin "2") (pinfunction "VCC_2") (pintype "passive"))
      (node (ref "U8") (pin "3") (pinfunction "VCC_3") (pintype "passive"))
    )
    (net (code "75") (name "unconnected-(C4-Pad1)") (class "Default")
      (node (ref "C4") (pin "1") (pinfunction "1_1") (pintype "passive"))
    )
    (net (code "76") (name "unconnected-(K1-A-Pad11)") (class "Default")
      (node (ref "K1") (pin "11") (pinfunction "A_11") (pintype "passive+no_connect"))
    )
    (net (code "77") (name "unconnected-(K1-B-Pad7)") (class "Default")
      (node (ref "K1") (pin "7") (pinfunction "B_7") (pintype "passive+no_connect"))
    )
    (net (code "78") (name "unconnected-(K1-C-Pad4)") (class "Default")
      (node (ref "K1") (pin "4") (pinfunction "C_4") (pintype "passive+no_connect"))
    )
    (net (code "79") (name "unconnected-(K1-D-Pad2)") (class "Default")
      (node (ref "K1") (pin "2") (pinfunction "D_2") (pintype "passive+no_connect"))
    )
    (net (code "80") (name "unconnected-(K1-DP-Pad3)") (class "Default")
      (node (ref "K1") (pin "3") (pinfunction "DP_3") (pintype "passive+no_connect"))
    )
    (net (code "81") (name "unconnected-(K1-E-Pad1)") (class "Default")
      (node (ref "K1") (pin "1") (pinfunction "E_1") (pintype "passive+no_connect"))
    )
    (net (code "82") (name "unconnected-(K1-F-Pad10)") (class "Default")
      (node (ref "K1") (pin "10") (pinfunction "F_10") (pintype "passive+no_connect"))
    )
    (net (code "83") (name "unconnected-(K1-G-Pad5)") (class "Default")
      (node (ref "K1") (pin "5") (pinfunction "G_5") (pintype "passive+no_connect"))
    )
    (net (code "84") (name "unconnected-(P0-Pad1)") (class "Default")
      (node (ref "P0") (pin "1") (pinfunction "1_1") (pintype "passive+no_connect"))
    )
    (net (code "85") (name "unconnected-(P0-Pad2)") (class "Default")
      (node (ref "P0") (pin "2") (pinfunction "2_2") (pintype "passive+no_connect"))
    )
    (net (code "86") (name "unconnected-(P0-Pad3)") (class "Default")
      (node (ref "P0") (pin "3") (pinfunction "3_3") (pintype "passive+no_connect"))
    )
    (net (code "87") (name "unconnected-(P0-Pad4)") (class "Default")
      (node (ref "P0") (pin "4") (pinfunction "4_4") (pintype "passive+no_connect"))
    )
    (net (code "88") (name "unconnected-(P0-Pad5)") (class "Default")
      (node (ref "P0") (pin "5") (pinfunction "5_5") (pintype "passive+no_connect"))
    )
    (net (code "89") (name "unconnected-(P0-Pad6)") (class "Default")
      (node (ref "P0") (pin "6") (pinfunction "6_6") (pintype "passive+no_connect"))
    )
    (net (code "90") (name "unconnected-(P0-Pad7)") (class "Default")
      (node (ref "P0") (pin "7") (pinfunction "7_7") (pintype "passive+no_connect"))
    )
    (net (code "91") (name "unconnected-(P0-Pad8)") (class "Default")
      (node (ref "P0") (pin "8") (pinfunction "8_8") (pintype "passive+no_connect"))
    )
    (net (code "92") (name "unconnected-(P2-Pad3)") (class "Default")
      (node (ref "P2") (pin "3") (pinfunction "3_3") (pintype "passive+no_connect"))
    )
    (net (code "93") (name "unconnected-(P3-Pad1)") (class "Default")
      (node (ref "P3") (pin "1") (pinfunction "1_1") (pintype "passive+no_connect"))
    )
    (net (code "94") (name "unconnected-(S21-A-Pad3)") (class "Default")
      (node (ref "S21-A") (pin "3") (pinfunction "3_3") (pintype "passive"))
    )
    (net (code "95") (name "unconnected-(S21-A-Pad5)") (class "Default")
      (node (ref "S21-A") (pin "5") (pinfunction "5_5") (pintype "passive"))
    )
    (net (code "96") (name "unconnected-(U1-P2.2-Pad23)") (class "Default")
      (node (ref "U1") (pin "23") (pinfunction "P2.2_23") (pintype "passive+no_connect"))
    )
    (net (code "97") (name "unconnected-(U1-RES-Pad9)") (class "Default")
      (node (ref "U1") (pin "9") (pinfunction "RES_9") (pintype "passive+no_connect"))
    )
    (net (code "98") (name "unconnected-(U1-RXD-Pad10)") (class "Default")
      (node (ref "U1") (pin "10") (pinfunction "RXD_10") (pintype "passive+no_connect"))
    )
    (net (code "99") (name "unconnected-(U1-~{ALE}-Pad30)") (class "Default")
      (node (ref "U1") (pin "30") (pinfunction "~{ALE}_30") (pintype "passive+no_connect"))
    )
    (net (code "100") (name "unconnected-(U1-~{EA}-Pad31)") (class "Default")
      (node (ref "U1") (pin "31") (pinfunction "~{EA}_31") (pintype "passive+no_connect"))
    )
    (net (code "101") (name "unconnected-(U1-~{PSEN}-Pad29)") (class "Default")
      (node (ref "U1") (pin "29") (pinfunction "~{PSEN}_29") (pintype "passive+no_connect"))
    )
    (net (code "102") (name "unconnected-(U2-CTS#-Pad9)") (class "Default")
      (node (ref "U2") (pin "9") (pinfunction "CTS#_9") (pintype "passive+no_connect"))
    )
    (net (code "103") (name "unconnected-(U2-DCD#-Pad12)") (class "Default")
      (node (ref "U2") (pin "12") (pinfunction "DCD#_12") (pintype "passive+no_connect"))
    )
    (net (code "104") (name "unconnected-(U2-DSR#-Pad10)") (class "Default")
      (node (ref "U2") (pin "10") (pinfunction "DSR#_10") (pintype "passive+no_connect"))
    )
    (net (code "105") (name "unconnected-(U2-DTR#-Pad13)") (class "Default")
      (node (ref "U2") (pin "13") (pinfunction "DTR#_13") (pintype "passive+no_connect"))
    )
    (net (code "106") (name "unconnected-(U2-R232-Pad15)") (class "Default")
      (node (ref "U2") (pin "15") (pinfunction "R232_15") (pintype "passive"))
    )
    (net (code "107") (name "unconnected-(U2-RI#-Pad11)") (class "Default")
      (node (ref "U2") (pin "11") (pinfunction "RI#_11") (pintype "passive+no_connect"))
    )
    (net (code "108") (name "unconnected-(U2-RTS#-Pad14)") (class "Default")
      (node (ref "U2") (pin "14") (pinfunction "RTS#_14") (pintype "passive+no_connect"))
    )
    (net (code "109") (name "unconnected-(U6-DB0-Pad7)") (class "Default")
      (node (ref "U6") (pin "7") (pinfunction "DB0_7") (pintype "passive+no_connect"))
    )
    (net (code "110") (name "unconnected-(U6-DB1-Pad8)") (class "Default")
      (node (ref "U6") (pin "8") (pinfunction "DB1_8") (pintype "passive+no_connect"))
    )
    (net (code "111") (name "unconnected-(U6-DB2-Pad9)") (class "Default")
      (node (ref "U6") (pin "9") (pinfunction "DB2_9") (pintype "passive+no_connect"))
    )
    (net (code "112") (name "unconnected-(U6-DB3-Pad10)") (class "Default")
      (node (ref "U6") (pin "10") (pinfunction "DB3_10") (pintype "passive+no_connect"))
    )
    (net (code "113") (name "unconnected-(U6-DB4-Pad11)") (class "Default")
      (node (ref "U6") (pin "11") (pinfunction "DB4_11") (pintype "passive+no_connect"))
    )
    (net (code "114") (name "unconnected-(U6-DB5-Pad12)") (class "Default")
      (node (ref "U6") (pin "12") (pinfunction "DB5_12") (pintype "passive+no_connect"))
    )
    (net (code "115") (name "unconnected-(U6-DB6-Pad13)") (class "Default")
      (node (ref "U6") (pin "13") (pinfunction "DB6_13") (pintype "passive+no_connect"))
    )
    (net (code "116") (name "unconnected-(U6-DB7-Pad14)") (class "Default")
      (node (ref "U6") (pin "14") (pinfunction "DB7_14") (pintype "passive+no_connect"))
    )
    (net (code "117") (name "unconnected-(U6-LED+-Pad15)") (class "Default")
      (node (ref "U6") (pin "15") (pinfunction "LED+_15") (pintype "passive+no_connect"))
    )
    (net (code "118") (name "unconnected-(U6-VCC-Pad2)") (class "Default")
      (node (ref "U6") (pin "2") (pinfunction "VCC_2") (pintype "passive+no_connect"))
    )
    (net (code "119") (name "unconnected-(U7-DB0-Pad7)") (class "Default")
      (node (ref "U7") (pin "7") (pinfunction "DB0_7") (pintype "passive+no_connect"))
    )
    (net (code "120") (name "unconnected-(U7-DB1-Pad8)") (class "Default")
      (node (ref "U7") (pin "8") (pinfunction "DB1_8") (pintype "passive+no_connect"))
    )
    (net (code "121") (name "unconnected-(U7-DB2-Pad9)") (class "Default")
      (node (ref "U7") (pin "9") (pinfunction "DB2_9") (pintype "passive+no_connect"))
    )
    (net (code "122") (name "unconnected-(U7-DB3-Pad10)") (class "Default")
      (node (ref "U7") (pin "10") (pinfunction "DB3_10") (pintype "passive+no_connect"))
    )
    (net (code "123") (name "unconnected-(U7-DB4-Pad11)") (class "Default")
      (node (ref "U7") (pin "11") (pinfunction "DB4_11") (pintype "passive+no_connect"))
    )
    (net (code "124") (name "unconnected-(U7-DB5-Pad12)") (class "Default")
      (node (ref "U7") (pin "12") (pinfunction "DB5_12") (pintype "passive+no_connect"))
    )
    (net (code "125") (name "unconnected-(U7-DB6-Pad13)") (class "Default")
      (node (ref "U7") (pin "13") (pinfunction "DB6_13") (pintype "passive+no_connect"))
    )
    (net (code "126") (name "unconnected-(U7-DB7-Pad14)") (class "Default")
      (node (ref "U7") (pin "14") (pinfunction "DB7_14") (pintype "passive+no_connect"))
    )
    (net (code "127") (name "unconnected-(U7-LED-A-Pad19)") (class "Default")
      (node (ref "U7") (pin "19") (pinfunction "LED-A_19") (pintype "passive+no_connect"))
    )
    (net (code "128") (name "unconnected-(U7-NC2-Pad18)") (class "Default")
      (node (ref "U7") (pin "18") (pinfunction "NC2_18") (pintype "passive+no_connect"))
    )
  )
)
